# waterius-factory-2_0wago.net
KiCad netlist of a schematic drawn in EAGLE
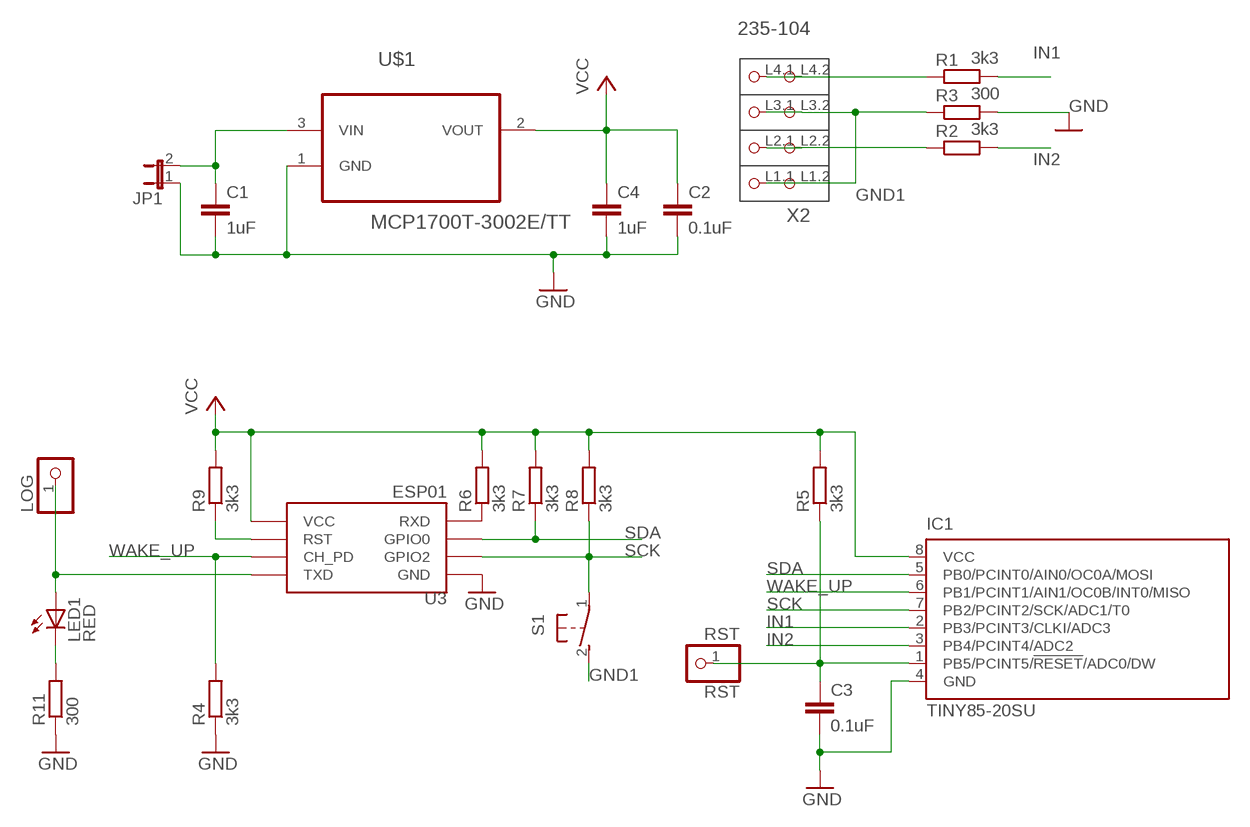
[diagram p0: schematic, sheet 1]

(export (version "E")
  (design (tool "Eeschema 10.0.6"))
  (components
    (comp (ref "C1")
      (value "1uF")
      (footprint "eagle-import:C0805")
      (libsource (lib "eagle-import") (part "C-EUC0805"))
    )
    (comp (ref "C2")
      (value "0.1uF")
      (footprint "eagle-import:C0805")
      (libsource (lib "eagle-import") (part "C-EUC0805"))
    )
    (comp (ref "C3")
      (value "0.1uF")
      (footprint "eagle-import:C0805")
      (libsource (lib "eagle-import") (part "C-EUC0805"))
    )
    (comp (ref "C4")
      (value "1uF")
      (footprint "eagle-import:C0805")
      (libsource (lib "eagle-import") (part "C-EUC0805"))
    )
    (comp (ref "IC1")
      (value "TINY85-20SU")
      (footprint "eagle-import:8S2")
      (fields (field (name "MPN") "ATTINY13-20SU"))
      (libsource (lib "eagle-import") (part "TINY13SU-20"))
    )
    (comp (ref "JP1")
      (value "JP1E")
      (footprint "eagle-import:JP1")
      (libsource (lib "eagle-import") (part "JP1E"))
    )
    (comp (ref "LED1")
      (value "RED")
      (footprint "eagle-import:LED3MM")
      (libsource (lib "eagle-import") (part "LED3MM"))
    )
    (comp (ref "LOG")
      (value "PINHD-1X1")
      (footprint "eagle-import:1X01")
      (libsource (lib "eagle-import") (part "PINHD-1X1"))
    )
    (comp (ref "R1")
      (value "3k3")
      (footprint "eagle-import:R0805")
      (libsource (lib "eagle-import") (part "R-EU_R0805"))
    )
    (comp (ref "R2")
      (value "3k3")
      (footprint "eagle-import:R0805")
      (libsource (lib "eagle-import") (part "R-EU_R0805"))
    )
    (comp (ref "R3")
      (value "300")
      (footprint "eagle-import:R0805")
      (libsource (lib "eagle-import") (part "R-EU_R0805"))
    )
    (comp (ref "R4")
      (value "3k3")
      (footprint "eagle-import:R0805")
      (libsource (lib "eagle-import") (part "R-EU_R0805"))
    )
    (comp (ref "R5")
      (value "3k3")
      (footprint "eagle-import:R0805")
      (libsource (lib "eagle-import") (part "R-EU_R0805"))
    )
    (comp (ref "R6")
      (value "3k3")
      (footprint "eagle-import:R0805")
      (libsource (lib "eagle-import") (part "R-EU_R0805"))
    )
    (comp (ref "R7")
      (value "3k3")
      (footprint "eagle-import:R0805")
      (libsource (lib "eagle-import") (part "R-EU_R0805"))
    )
    (comp (ref "R8")
      (value "3k3")
      (footprint "eagle-import:R0805")
      (libsource (lib "eagle-import") (part "R-EU_R0805"))
    )
    (comp (ref "R9")
      (value "3k3")
      (footprint "eagle-import:R0805")
      (libsource (lib "eagle-import") (part "R-EU_R0805"))
    )
    (comp (ref "R11")
      (value "300")
      (footprint "eagle-import:R0805")
      (libsource (lib "eagle-import") (part "R-EU_R0805"))
    )
    (comp (ref "RST")
      (value "RST")
      (footprint "eagle-import:1X01")
      (libsource (lib "eagle-import") (part "PINHD-1X1"))
    )
    (comp (ref "S1")
      (value "31-XX")
      (footprint "eagle-import:B3F-31XX")
      (fields (field (name "MPN") "B3F-3100"))
      (libsource (lib "eagle-import") (part "31-XX"))
    )
    (comp (ref "U$1")
      (value "MCP1700T-3002E/TT")
      (footprint "eagle-import:SOT95P237X112-3N")
      (fields (field (name "MF") "Microchip"))
      (libsource (lib "eagle-import") (part "MCP1700T-3002E/TT"))
    )
    (comp (ref "U3")
      (value "ESP01")
      (footprint "eagle-import:ESP01")
      (libsource (lib "eagle-import") (part "ESP01"))
    )
    (comp (ref "X2")
      (value "235-104")
      (footprint "eagle-import:P-235-104")
      (libsource (lib "eagle-import") (part "235-104"))
    )
  )
  (nets
    (net (code "1") (name "/GND1") (class "Default")
      (node (ref "R3") (pin "1") (pinfunction "1_1") (pintype "passive"))
      (node (ref "S1") (pin "2") (pinfunction "S_2") (pintype "passive"))
      (node (ref "X2") (pin "L1.1") (pinfunction "P1.1_L1.1") (pintype "bidirectional"))
      (node (ref "X2") (pin "L1.2") (pinfunction "P1.2_L1.2") (pintype "bidirectional"))
      (node (ref "X2") (pin "L3.1") (pinfunction "P3.1_L3.1") (pintype "bidirectional"))
      (node (ref "X2") (pin "L3.2") (pinfunction "P3.2_L3.2") (pintype "bidirectional"))
    )
    (net (code "2") (name "/IN1") (class "Default")
      (node (ref "IC1") (pin "2") (pinfunction "PB3/PCINT3/CLKI/ADC3_2") (pintype "bidirectional"))
      (node (ref "R1") (pin "2") (pinfunction "2_2") (pintype "passive"))
    )
    (net (code "3") (name "/IN2") (class "Default")
      (node (ref "IC1") (pin "3") (pinfunction "PB4/PCINT4/ADC2_3") (pintype "bidirectional"))
      (node (ref "R2") (pin "2") (pinfunction "2_2") (pintype "passive"))
    )
    (net (code "4") (name "/SCK") (class "Default")
      (node (ref "IC1") (pin "7") (pinfunction "PB2/PCINT2/SCK/ADC1/T0_7") (pintype "bidirectional"))
      (node (ref "R8") (pin "1") (pinfunction "1_1") (pintype "passive"))
      (node (ref "S1") (pin "1") (pinfunction "P_1") (pintype "passive"))
      (node (ref "U3") (pin "GPIO2") (pinfunction "GPIO2_GPIO2") (pintype "bidirectional"))
    )
    (net (code "5") (name "/SDA") (class "Default")
      (node (ref "IC1") (pin "5") (pinfunction "PB0/PCINT0/AIN0/OC0A/MOSI_5") (pintype "bidirectional"))
      (node (ref "R7") (pin "1") (pinfunction "1_1") (pintype "passive"))
      (node (ref "U3") (pin "GPIO0") (pinfunction "GPIO0_GPIO0") (pintype "bidirectional"))
    )
    (net (code "6") (name "/WAKE_UP") (class "Default")
      (node (ref "IC1") (pin "6") (pinfunction "PB1/PCINT1/AIN1/OC0B/INT0/MISO_6") (pintype "bidirectional"))
      (node (ref "R4") (pin "2") (pinfunction "2_2") (pintype "passive"))
      (node (ref "U3") (pin "CH_PD") (pinfunction "CH_PD_CH_PD") (pintype "bidirectional"))
    )
    (net (code "7") (name "GND") (class "Default")
      (node (ref "C1") (pin "2") (pinfunction "2_2") (pintype "passive"))
      (node (ref "C2") (pin "2") (pinfunction "2_2") (pintype "passive"))
      (node (ref "C3") (pin "2") (pinfunction "2_2") (pintype "passive"))
      (node (ref "C4") (pin "2") (pinfunction "2_2") (pintype "passive"))
      (node (ref "IC1") (pin "4") (pinfunction "GND_4") (pintype "power_in"))
      (node (ref "JP1") (pin "1") (pinfunction "1_1") (pintype "passive"))
      (node (ref "R11") (pin "1") (pinfunction "1_1") (pintype "passive"))
      (node (ref "R3") (pin "2") (pinfunction "2_2") (pintype "passive"))
      (node (ref "R4") (pin "1") (pinfunction "1_1") (pintype "passive"))
      (node (ref "U$1") (pin "1") (pinfunction "GND_1") (pintype "passive"))
      (node (ref "U3") (pin "GND") (pinfunction "GND_GND") (pintype "bidirectional"))
    )
    (net (code "8") (name "Net-(IC1-PB5{slash}PCINT5{slash}~{RESET}{slash}ADC0{slash}DW)") (class "Default")
      (node (ref "C3") (pin "1") (pinfunction "1_1") (pintype "passive"))
      (node (ref "IC1") (pin "1") (pinfunction "PB5/PCINT5/~{RESET}/ADC0/DW_1") (pintype "bidirectional"))
      (node (ref "R5") (pin "1") (pinfunction "1_1") (pintype "passive"))
      (node (ref "RST") (pin "1") (pinfunction "1_1") (pintype "passive"))
    )
    (net (code "9") (name "Net-(LED1-C)") (class "Default")
      (node (ref "LED1") (pin "K") (pinfunction "C_K") (pintype "passive"))
      (node (ref "R11") (pin "2") (pinfunction "2_2") (pintype "passive"))
    )
    (net (code "10") (name "Net-(R9-Pad1)") (class "Default")
      (node (ref "R9") (pin "1") (pinfunction "1_1") (pintype "passive"))
      (node (ref "U3") (pin "RST") (pinfunction "RST_RST") (pintype "bidirectional"))
    )
    (net (code "11") (name "Net-(U$1-VIN)") (class "Default")
      (node (ref "C1") (pin "1") (pinfunction "1_1") (pintype "passive"))
      (node (ref "JP1") (pin "2") (pinfunction "2_2") (pintype "passive"))
      (node (ref "U$1") (pin "3") (pinfunction "VIN_3") (pintype "input"))
    )
    (net (code "12") (name "Net-(U3-RXD)") (class "Default")
      (node (ref "R6") (pin "1") (pinfunction "1_1") (pintype "passive"))
      (node (ref "U3") (pin "RX") (pinfunction "RXD_RX") (pintype "bidirectional"))
    )
    (net (code "13") (name "Net-(U3-TXD)") (class "Default")
      (node (ref "LED1") (pin "A") (pinfunction "A_A") (pintype "passive"))
      (node (ref "LOG") (pin "1") (pinfunction "1_1") (pintype "passive"))
      (node (ref "U3") (pin "TX") (pinfunction "TXD_TX") (pintype "bidirectional"))
    )
    (net (code "14") (name "Net-(X2-P2.1)") (class "Default")
      (node (ref "R2") (pin "1") (pinfunction "1_1") (pintype "passive"))
      (node (ref "X2") (pin "L2.1") (pinfunction "P2.1_L2.1") (pintype "bidirectional"))
      (node (ref "X2") (pin "L2.2") (pinfunction "P2.2_L2.2") (pintype "bidirectional"))
    )
    (net (code "15") (name "Net-(X2-P4.1)") (class "Default")
      (node (ref "R1") (pin "1") (pinfunction "1_1") (pintype "passive"))
      (node (ref "X2") (pin "L4.1") (pinfunction "P4.1_L4.1") (pintype "bidirectional"))
      (node (ref "X2") (pin "L4.2") (pinfunction "P4.2_L4.2") (pintype "bidirectional"))
    )
    (net (code "16") (name "VCC") (class "Default")
      (node (ref "C2") (pin "1") (pinfunction "1_1") (pintype "passive"))
      (node (ref "C4") (pin "1") (pinfunction "1_1") (pintype "passive"))
      (node (ref "IC1") (pin "8") (pinfunction "VCC_8") (pintype "power_in"))
      (node (ref "R5") (pin "2") (pinfunction "2_2") (pintype "passive"))
      (node (ref "R6") (pin "2") (pinfunction "2_2") (pintype "passive"))
      (node (ref "R7") (pin "2") (pinfunction "2_2") (pintype "passive"))
      (node (ref "R8") (pin "2") (pinfunction "2_2") (pintype "passive"))
      (node (ref "R9") (pin "2") (pinfunction "2_2") (pintype "passive"))
      (node (ref "U$1") (pin "2") (pinfunction "VOUT_2") (pintype "output"))
      (node (ref "U3") (pin "VCC") (pinfunction "VCC_VCC") (pintype "bidirectional"))
    )
  )
)
